# Motor-Board-Rev1.net
KiCad netlist of a schematic drawn in EAGLE
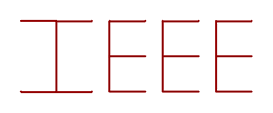
[diagram p0: schematic, sheet 1]
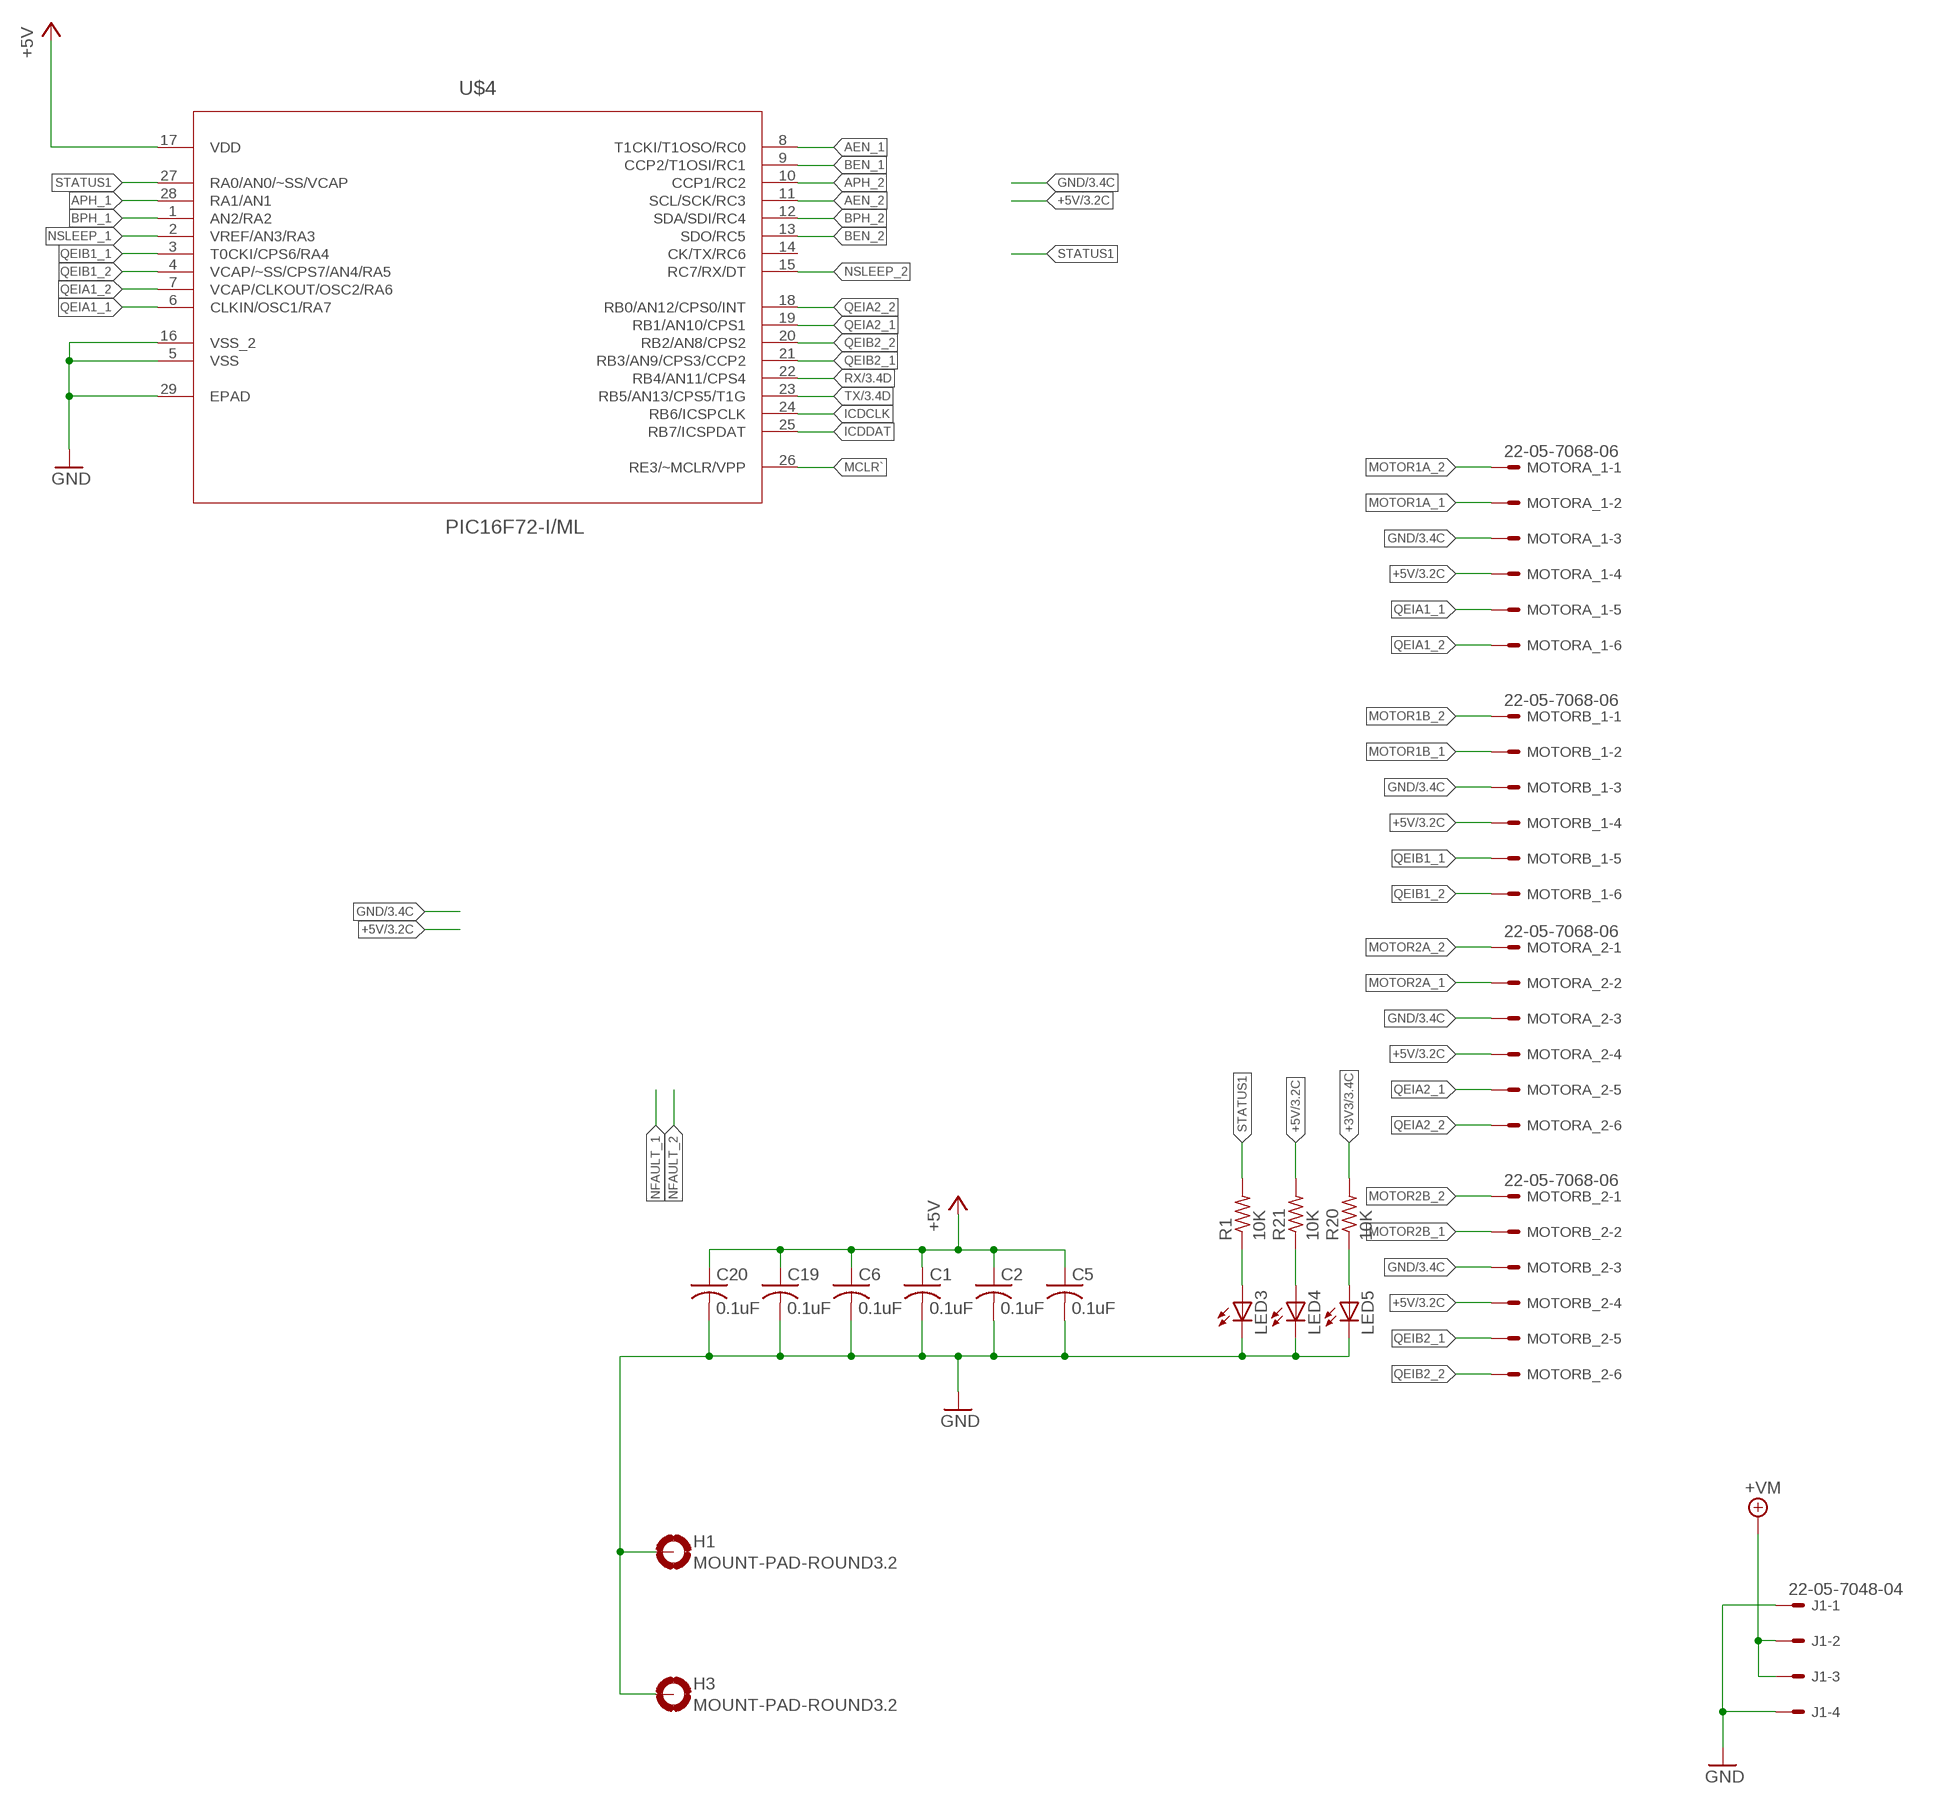
[diagram p1: schematic, sheet 2, part 1 of 2]
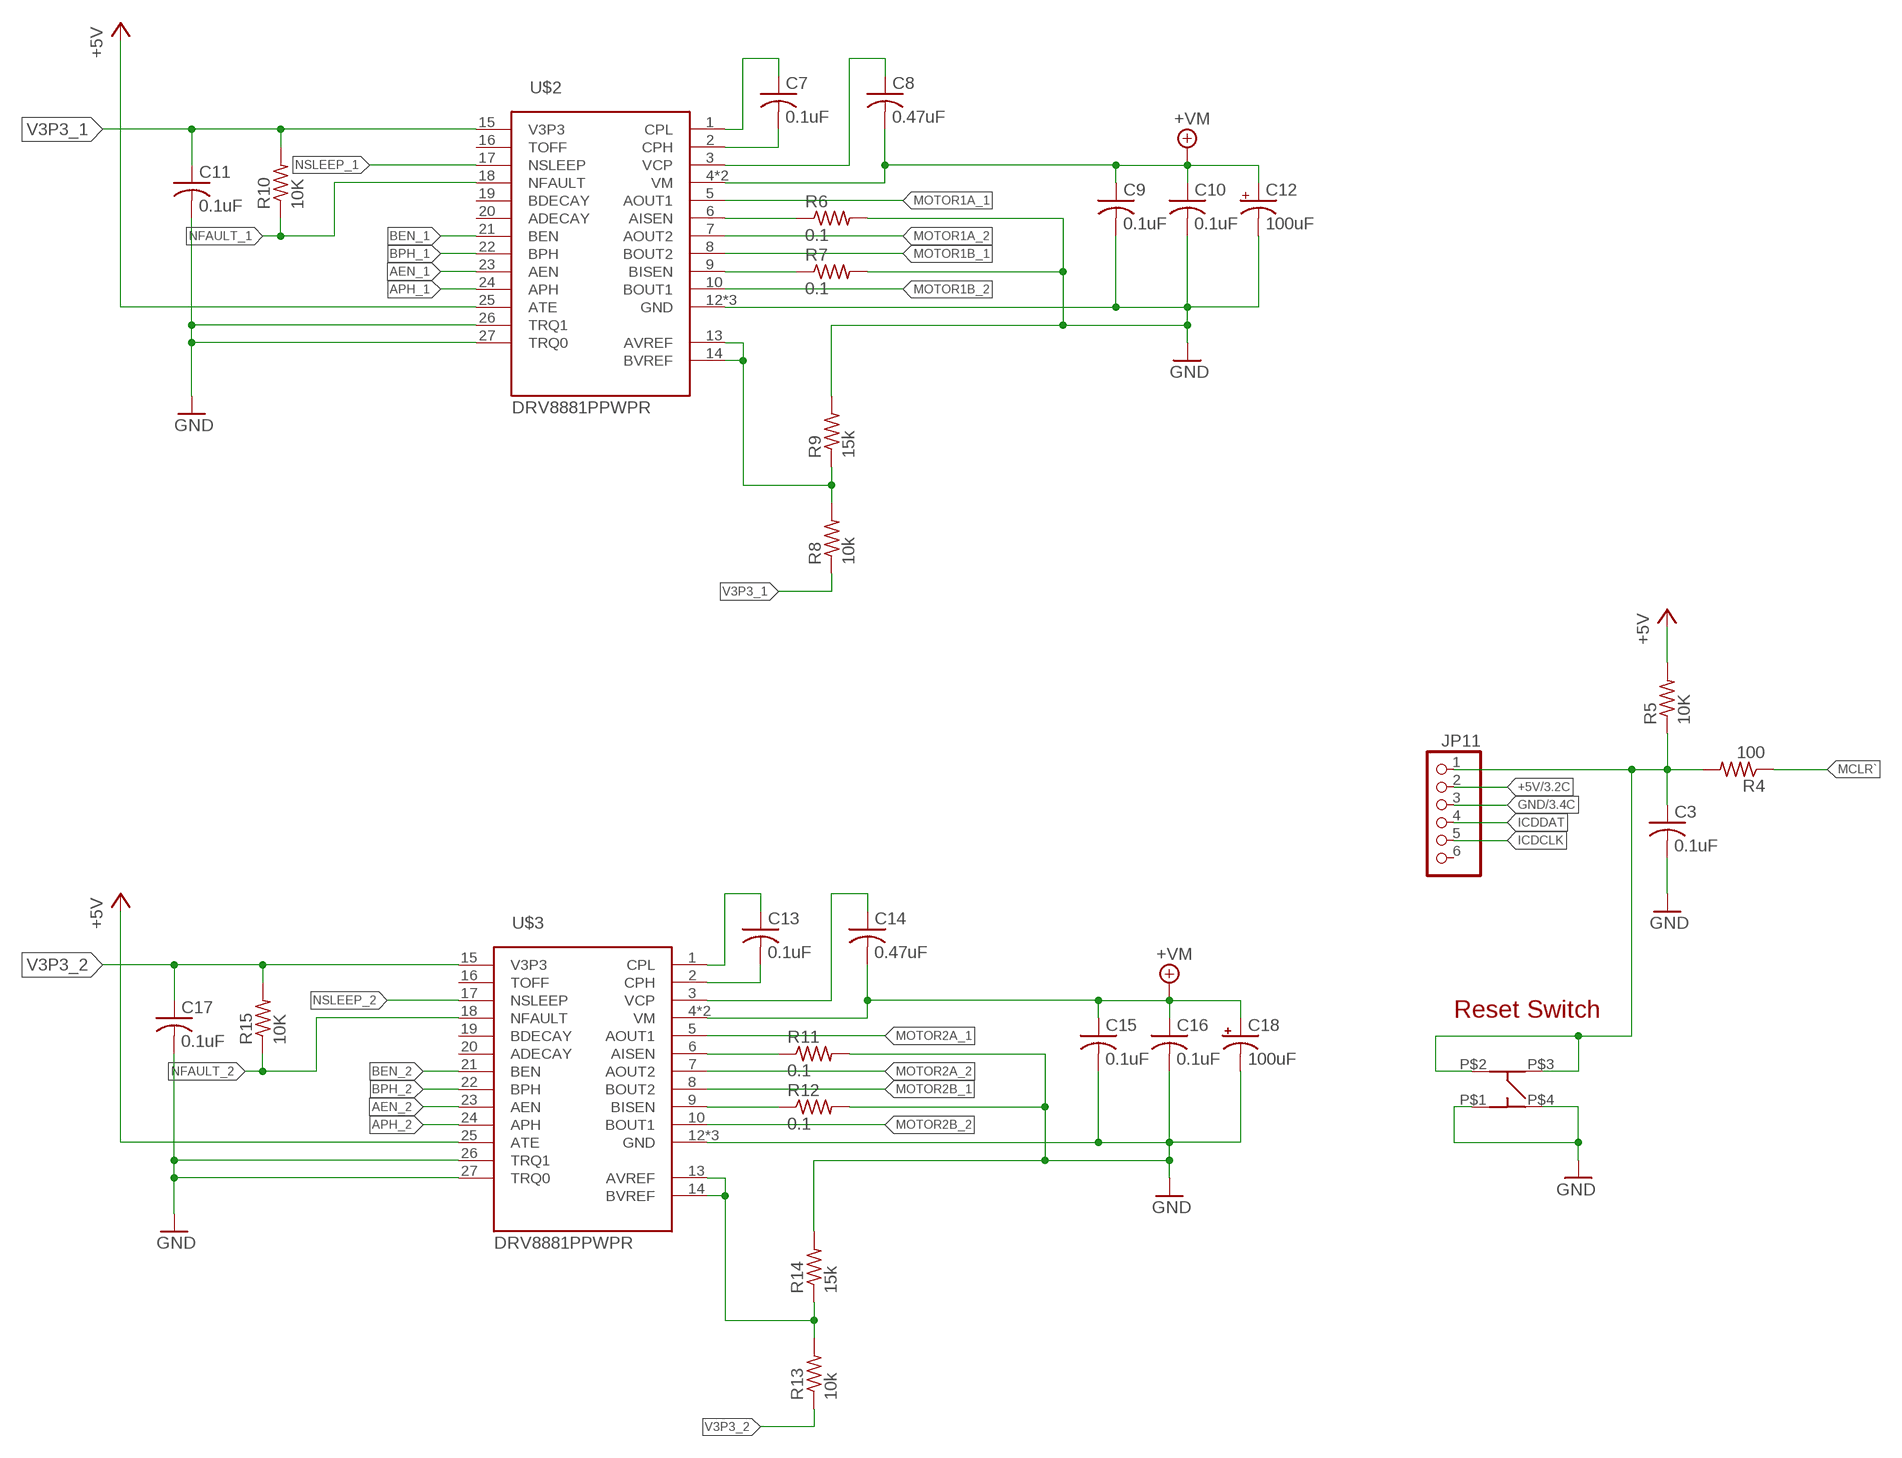
[diagram p2: schematic, sheet 2, part 2 of 2]
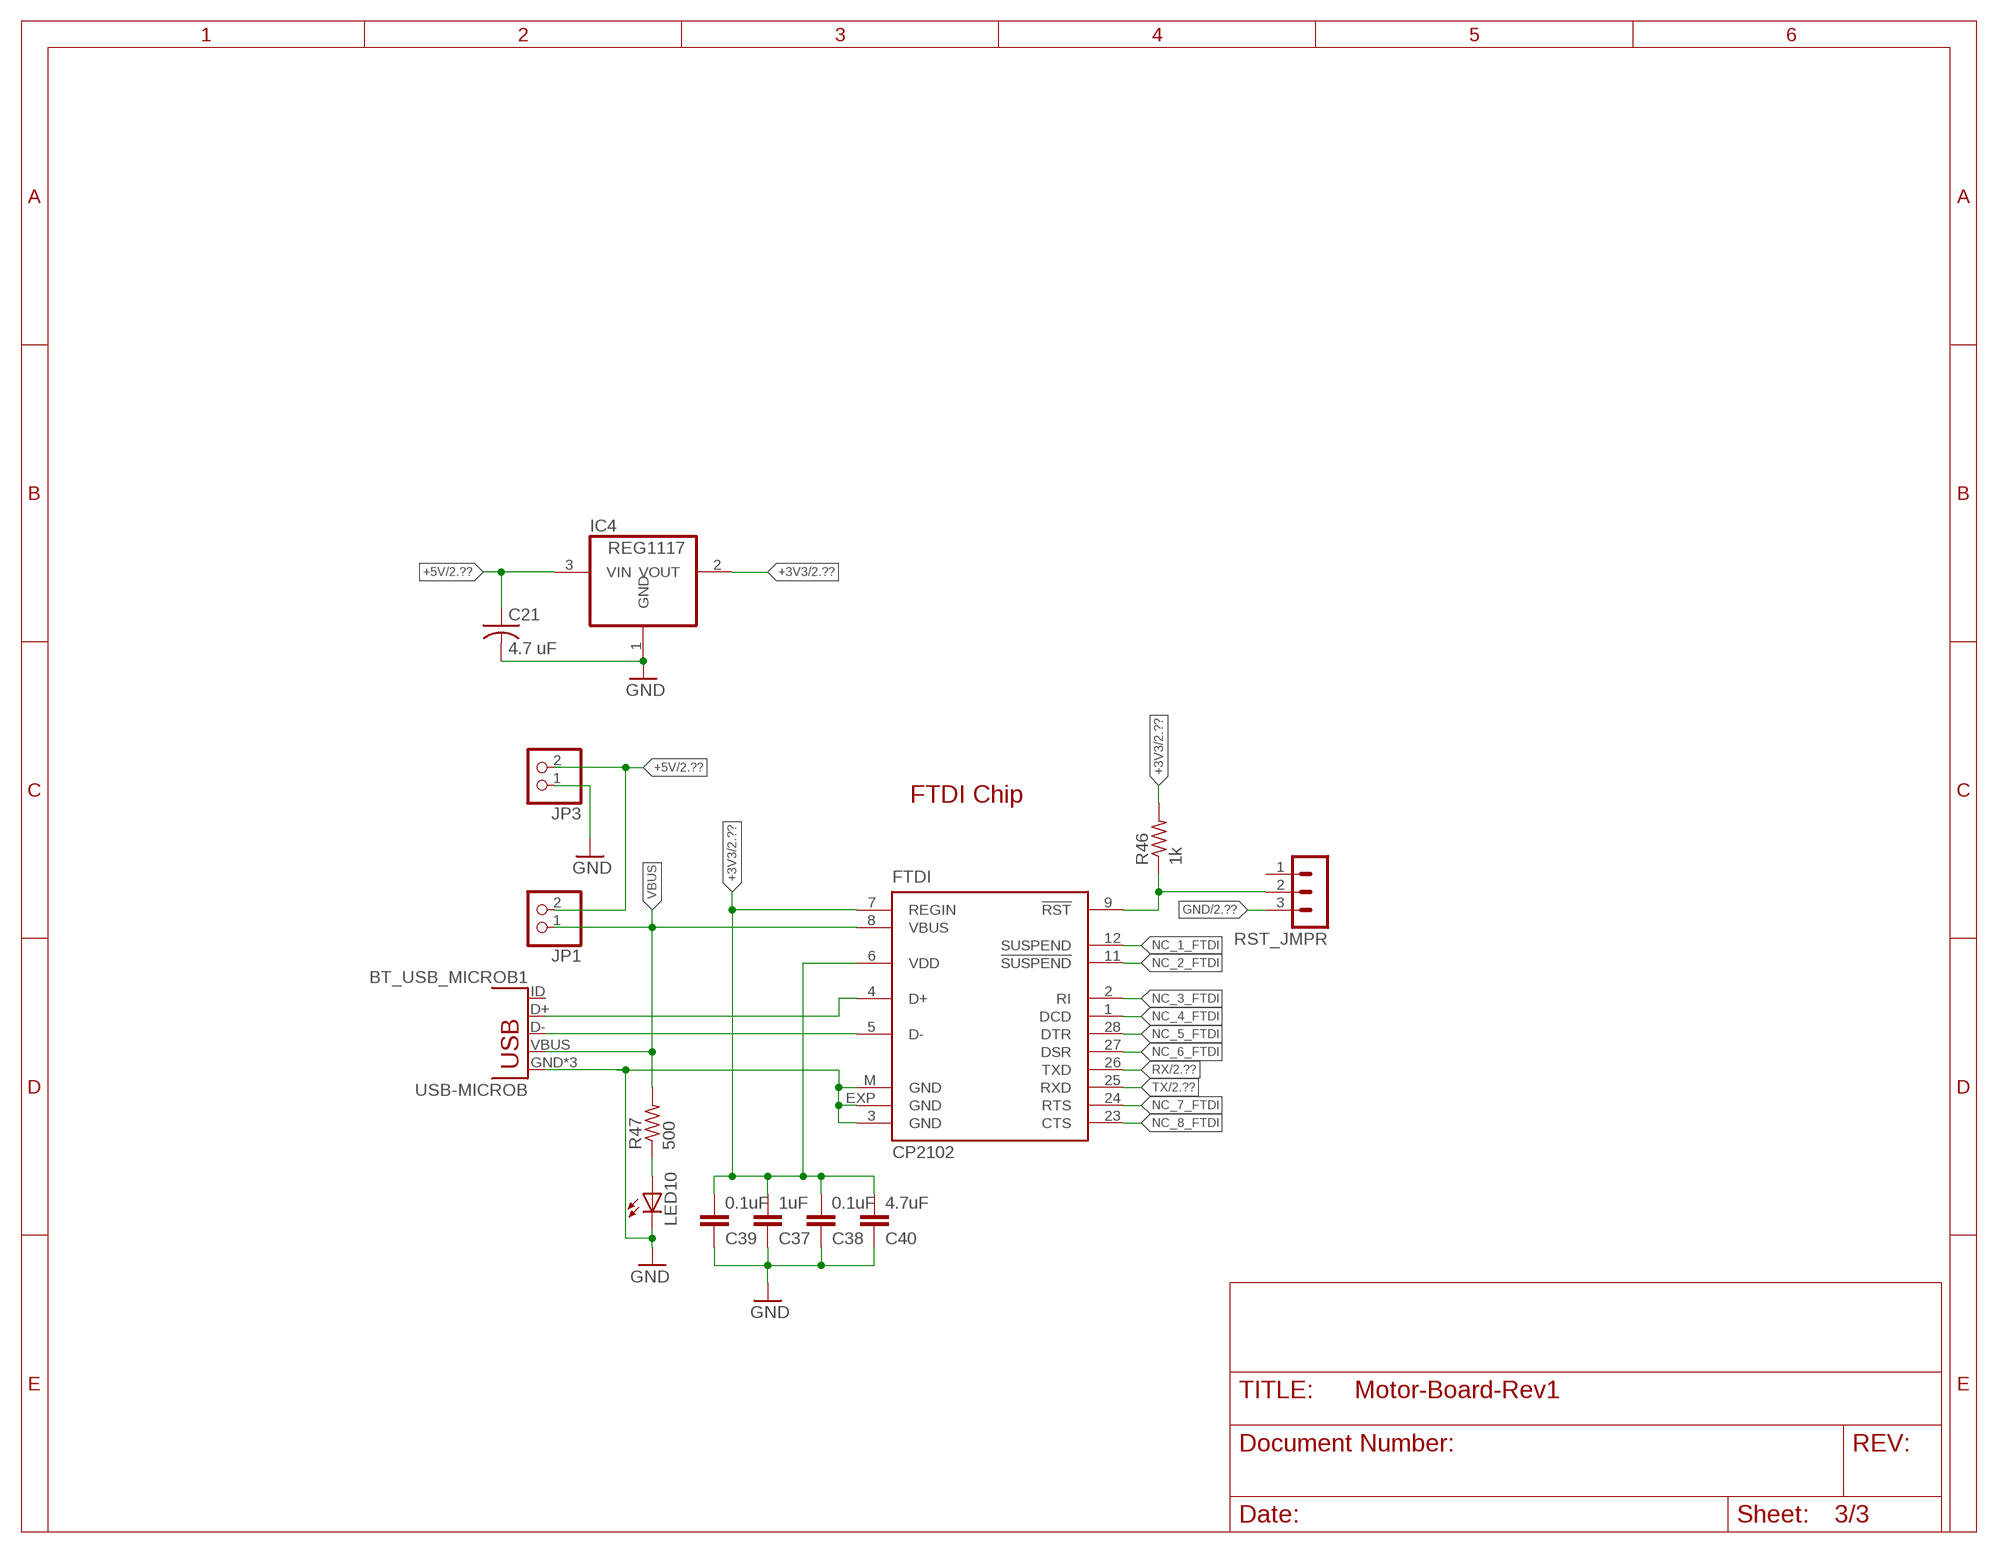
[diagram p3: schematic, sheet 3]

(export (version "E")
  (design (tool "Eeschema 10.0.6"))
  (components
    (comp (ref "U$1")
      (value "LOGO")
      (footprint "eagle-import:IEEE-LOGO")
      (libsource (lib "eagle-import") (part "LOGO"))
    )
    (comp (ref "C1")
      (value "0.1uF")
      (footprint "eagle-import:C0805")
      (libsource (lib "eagle-import") (part "C-USC0805"))
    )
    (comp (ref "C2")
      (value "0.1uF")
      (footprint "eagle-import:C0805")
      (libsource (lib "eagle-import") (part "C-USC0805"))
    )
    (comp (ref "C3")
      (value "0.1uF")
      (footprint "eagle-import:C0805")
      (libsource (lib "eagle-import") (part "C-USC0805"))
    )
    (comp (ref "C5")
      (value "0.1uF")
      (footprint "eagle-import:C0805")
      (libsource (lib "eagle-import") (part "C-USC0805"))
    )
    (comp (ref "C6")
      (value "0.1uF")
      (footprint "eagle-import:C0805")
      (libsource (lib "eagle-import") (part "C-USC0805"))
    )
    (comp (ref "C7")
      (value "0.1uF")
      (footprint "eagle-import:C0402")
      (libsource (lib "eagle-import") (part "C-USC0402"))
    )
    (comp (ref "C8")
      (value "0.47uF")
      (footprint "eagle-import:C0402")
      (libsource (lib "eagle-import") (part "C-USC0402"))
    )
    (comp (ref "C9")
      (value "0.1uF")
      (footprint "eagle-import:C0402")
      (libsource (lib "eagle-import") (part "C-USC0402"))
    )
    (comp (ref "C10")
      (value "0.1uF")
      (footprint "eagle-import:C0402")
      (libsource (lib "eagle-import") (part "C-USC0402"))
    )
    (comp (ref "C11")
      (value "0.1uF")
      (footprint "eagle-import:C0402")
      (libsource (lib "eagle-import") (part "C-USC0402"))
    )
    (comp (ref "C12")
      (value "100uF")
      (footprint "eagle-import:EIA7343")
      (libsource (lib "eagle-import") (part "100UF-10V-10%(TANT)"))
    )
    (comp (ref "C13")
      (value "0.1uF")
      (footprint "eagle-import:C0402")
      (libsource (lib "eagle-import") (part "C-USC0402"))
    )
    (comp (ref "C14")
      (value "0.47uF")
      (footprint "eagle-import:C0402")
      (libsource (lib "eagle-import") (part "C-USC0402"))
    )
    (comp (ref "C15")
      (value "0.1uF")
      (footprint "eagle-import:C0402")
      (libsource (lib "eagle-import") (part "C-USC0402"))
    )
    (comp (ref "C16")
      (value "0.1uF")
      (footprint "eagle-import:C0402")
      (libsource (lib "eagle-import") (part "C-USC0402"))
    )
    (comp (ref "C17")
      (value "0.1uF")
      (footprint "eagle-import:C0402")
      (libsource (lib "eagle-import") (part "C-USC0402"))
    )
    (comp (ref "C18")
      (value "100uF")
      (footprint "eagle-import:EIA7343")
      (libsource (lib "eagle-import") (part "100UF-10V-10%(TANT)"))
    )
    (comp (ref "C19")
      (value "0.1uF")
      (footprint "eagle-import:C0805")
      (libsource (lib "eagle-import") (part "C-USC0805"))
    )
    (comp (ref "C20")
      (value "0.1uF")
      (footprint "eagle-import:C0805")
      (libsource (lib "eagle-import") (part "C-USC0805"))
    )
    (comp (ref "H1")
      (value "MOUNT-PAD-ROUND3.2")
      (footprint "eagle-import:3,2-PAD")
      (libsource (lib "eagle-import") (part "MOUNT-PAD-ROUND3.2"))
    )
    (comp (ref "H3")
      (value "MOUNT-PAD-ROUND3.2")
      (footprint "eagle-import:3,2-PAD")
      (libsource (lib "eagle-import") (part "MOUNT-PAD-ROUND3.2"))
    )
    (comp (ref "J1")
      (value "22-05-7048-04")
      (footprint "eagle-import:7395-04")
      (libsource (lib "eagle-import") (part "22-?-0405-7048"))
    )
    (comp (ref "JP11")
      (value "PINHD-1X6/90")
      (footprint "eagle-import:1X06_90")
      (libsource (lib "eagle-import") (part "PINHD-1X6/90"))
    )
    (comp (ref "LED3")
      (value "LEDSML0603")
      (footprint "eagle-import:SML0603")
      (libsource (lib "eagle-import") (part "LEDSML0603"))
    )
    (comp (ref "LED4")
      (value "LEDSML0603")
      (footprint "eagle-import:SML0603")
      (libsource (lib "eagle-import") (part "LEDSML0603"))
    )
    (comp (ref "LED5")
      (value "LEDSML0603")
      (footprint "eagle-import:SML0603")
      (libsource (lib "eagle-import") (part "LEDSML0603"))
    )
    (comp (ref "MOTORA_1")
      (value "22-05-7068-06")
      (footprint "eagle-import:7395-06")
      (libsource (lib "eagle-import") (part "22-?-0605-7068"))
    )
    (comp (ref "MOTORA_2")
      (value "22-05-7068-06")
      (footprint "eagle-import:7395-06")
      (libsource (lib "eagle-import") (part "22-?-0605-7068"))
    )
    (comp (ref "MOTORB_1")
      (value "22-05-7068-06")
      (footprint "eagle-import:7395-06")
      (libsource (lib "eagle-import") (part "22-?-0605-7068"))
    )
    (comp (ref "MOTORB_2")
      (value "22-05-7068-06")
      (footprint "eagle-import:7395-06")
      (libsource (lib "eagle-import") (part "22-?-0605-7068"))
    )
    (comp (ref "R1")
      (value "10K")
      (footprint "eagle-import:R0805")
      (libsource (lib "eagle-import") (part "R-US_R0805"))
    )
    (comp (ref "R4")
      (value "100")
      (footprint "eagle-import:R0805")
      (libsource (lib "eagle-import") (part "R-US_R0805"))
    )
    (comp (ref "R5")
      (value "10K")
      (footprint "eagle-import:R0805")
      (libsource (lib "eagle-import") (part "R-US_R0805"))
    )
    (comp (ref "R6")
      (value "0.1")
      (footprint "eagle-import:R1206")
      (libsource (lib "eagle-import") (part "R-US_R1206"))
    )
    (comp (ref "R7")
      (value "0.1")
      (footprint "eagle-import:R1206")
      (libsource (lib "eagle-import") (part "R-US_R1206"))
    )
    (comp (ref "R8")
      (value "10k")
      (footprint "eagle-import:R0402")
      (libsource (lib "eagle-import") (part "R-US_R0402"))
    )
    (comp (ref "R9")
      (value "15k")
      (footprint "eagle-import:R0402")
      (libsource (lib "eagle-import") (part "R-US_R0402"))
    )
    (comp (ref "R10")
      (value "10K")
      (footprint "eagle-import:R1206")
      (libsource (lib "eagle-import") (part "R-US_R1206"))
    )
    (comp (ref "R11")
      (value "0.1")
      (footprint "eagle-import:R1206")
      (libsource (lib "eagle-import") (part "R-US_R1206"))
    )
    (comp (ref "R12")
      (value "0.1")
      (footprint "eagle-import:R1206")
      (libsource (lib "eagle-import") (part "R-US_R1206"))
    )
    (comp (ref "R13")
      (value "10k")
      (footprint "eagle-import:R0402")
      (libsource (lib "eagle-import") (part "R-US_R0402"))
    )
    (comp (ref "R14")
      (value "15k")
      (footprint "eagle-import:R0402")
      (libsource (lib "eagle-import") (part "R-US_R0402"))
    )
    (comp (ref "R15")
      (value "10K")
      (footprint "eagle-import:R1206")
      (libsource (lib "eagle-import") (part "R-US_R1206"))
    )
    (comp (ref "R20")
      (value "10K")
      (footprint "eagle-import:R0805")
      (libsource (lib "eagle-import") (part "R-US_R0805"))
    )
    (comp (ref "R21")
      (value "10K")
      (footprint "eagle-import:R0805")
      (libsource (lib "eagle-import") (part "R-US_R0805"))
    )
    (comp (ref "TOUCH_RESET")
      (value "RESET")
      (footprint "eagle-import:MC32882_FINAL")
      (libsource (lib "eagle-import") (part "MC32882_SW"))
    )
    (comp (ref "U$2")
      (value "DRV8881PPWPR")
      (footprint "eagle-import:TSSOP-28")
      (libsource (lib "eagle-import") (part "DRV8881PPWPR"))
    )
    (comp (ref "U$3")
      (value "DRV8881PPWPR")
      (footprint "eagle-import:TSSOP-28")
      (libsource (lib "eagle-import") (part "DRV8881PPWPR"))
    )
    (comp (ref "U$4")
      (value "PIC16F72-I/ML")
      (footprint "eagle-import:QFN65P600X600X100-28N")
      (libsource (lib "eagle-import") (part "PIC16F72-I/ML"))
    )
    (comp (ref "BT_USB_MICROB1")
      (value "USB-MICROB")
      (footprint "eagle-import:USB-MICROB")
      (libsource (lib "eagle-import") (part "USB-MICROB"))
    )
    (comp (ref "C21")
      (value "4.7 uF")
      (footprint "eagle-import:C0805")
      (libsource (lib "eagle-import") (part "C-USC0805"))
    )
    (comp (ref "C37")
      (value "1uF")
      (footprint "eagle-import:C0805")
      (libsource (lib "eagle-import") (part "C-EUC0805"))
    )
    (comp (ref "C38")
      (value "0.1uF")
      (footprint "eagle-import:C0805")
      (libsource (lib "eagle-import") (part "C-EUC0805"))
    )
    (comp (ref "C39")
      (value "0.1uF")
      (footprint "eagle-import:C0805")
      (libsource (lib "eagle-import") (part "C-EUC0805"))
    )
    (comp (ref "C40")
      (value "4.7uF")
      (footprint "eagle-import:C0805")
      (libsource (lib "eagle-import") (part "C-EUC0805"))
    )
    (comp (ref "FTDI")
      (value "CP2102")
      (footprint "eagle-import:MLP28")
      (fields (field (name "MF") "FARNELL") (field (name "MPN") "CP2102-GM"))
      (libsource (lib "eagle-import") (part "CP2102"))
    )
    (comp (ref "IC4")
      (value "REG1117")
      (footprint "eagle-import:SOT223")
      (libsource (lib "eagle-import") (part "REG1117"))
    )
    (comp (ref "JP1")
      (value "PINHD-1X2")
      (footprint "eagle-import:1X02")
      (libsource (lib "eagle-import") (part "PINHD-1X2"))
    )
    (comp (ref "JP3")
      (value "PINHD-1X2")
      (footprint "eagle-import:1X02")
      (libsource (lib "eagle-import") (part "PINHD-1X2"))
    )
    (comp (ref "LED10")
      (value "LEDSML0603")
      (footprint "eagle-import:SML0603")
      (libsource (lib "eagle-import") (part "LEDSML0603"))
    )
    (comp (ref "R46")
      (value "1k")
      (footprint "eagle-import:R0805")
      (libsource (lib "eagle-import") (part "resistor_R-US_R0805"))
    )
    (comp (ref "R47")
      (value "500")
      (footprint "eagle-import:R0805")
      (libsource (lib "eagle-import") (part "resistor_R-US_R0805"))
    )
    (comp (ref "RST_JMPR")
      (value "MA03-1")
      (footprint "eagle-import:MA03-1")
      (libsource (lib "eagle-import") (part "MA03-1"))
    )
  )
  (nets
    (net (code "1") (name "+3V3") (class "Default")
      (node (ref "C37") (pin "2") (pinfunction "2_2") (pintype "passive"))
      (node (ref "C38") (pin "2") (pinfunction "2_2") (pintype "passive"))
      (node (ref "C39") (pin "2") (pinfunction "2_2") (pintype "passive"))
      (node (ref "C40") (pin "2") (pinfunction "2_2") (pintype "passive"))
      (node (ref "FTDI") (pin "6") (pinfunction "VDD_6") (pintype "power_in"))
      (node (ref "FTDI") (pin "7") (pinfunction "REGIN_7") (pintype "passive"))
      (node (ref "IC4") (pin "2") (pinfunction "VOUT_2") (pintype "output"))
      (node (ref "R20") (pin "2") (pinfunction "2_2") (pintype "passive"))
      (node (ref "R46") (pin "2") (pinfunction "2_2") (pintype "passive"))
    )
    (net (code "2") (name "+5V") (class "Default")
      (node (ref "C1") (pin "1") (pinfunction "1_1") (pintype "passive"))
      (node (ref "C19") (pin "1") (pinfunction "1_1") (pintype "passive"))
      (node (ref "C2") (pin "1") (pinfunction "1_1") (pintype "passive"))
      (node (ref "C20") (pin "1") (pinfunction "1_1") (pintype "passive"))
      (node (ref "C21") (pin "1") (pinfunction "1_1") (pintype "passive"))
      (node (ref "C5") (pin "1") (pinfunction "1_1") (pintype "passive"))
      (node (ref "C6") (pin "1") (pinfunction "1_1") (pintype "passive"))
      (node (ref "IC4") (pin "3") (pinfunction "VIN_3") (pintype "input"))
      (node (ref "JP1") (pin "2") (pinfunction "2_2") (pintype "passive"))
      (node (ref "JP11") (pin "2") (pinfunction "2_2") (pintype "passive"))
      (node (ref "JP3") (pin "2") (pinfunction "2_2") (pintype "passive"))
      (node (ref "MOTORA_1") (pin "4") (pinfunction "S_4") (pintype "passive"))
      (node (ref "MOTORA_2") (pin "4") (pinfunction "S_4") (pintype "passive"))
      (node (ref "MOTORB_1") (pin "4") (pinfunction "S_4") (pintype "passive"))
      (node (ref "MOTORB_2") (pin "4") (pinfunction "S_4") (pintype "passive"))
      (node (ref "R21") (pin "2") (pinfunction "2_2") (pintype "passive"))
      (node (ref "R5") (pin "2") (pinfunction "2_2") (pintype "passive"))
      (node (ref "U$2") (pin "25") (pinfunction "ATE_25") (pintype "bidirectional"))
      (node (ref "U$3") (pin "25") (pinfunction "ATE_25") (pintype "bidirectional"))
      (node (ref "U$4") (pin "17") (pinfunction "VDD_17") (pintype "power_in"))
    )
    (net (code "3") (name "+7V") (class "Default")
      (node (ref "C10") (pin "1") (pinfunction "1_1") (pintype "passive"))
      (node (ref "C12") (pin "A") (pinfunction "+_A") (pintype "passive"))
      (node (ref "C14") (pin "2") (pinfunction "2_2") (pintype "passive"))
      (node (ref "C15") (pin "1") (pinfunction "1_1") (pintype "passive"))
      (node (ref "C16") (pin "1") (pinfunction "1_1") (pintype "passive"))
      (node (ref "C18") (pin "A") (pinfunction "+_A") (pintype "passive"))
      (node (ref "C8") (pin "2") (pinfunction "2_2") (pintype "passive"))
      (node (ref "C9") (pin "1") (pinfunction "1_1") (pintype "passive"))
      (node (ref "J1") (pin "2") (pinfunction "S_2") (pintype "passive"))
      (node (ref "J1") (pin "3") (pinfunction "S_3") (pintype "passive"))
      (node (ref "U$2") (pin "11") (pinfunction "VM_11") (pintype "bidirectional"))
      (node (ref "U$2") (pin "4") (pinfunction "VM_4") (pintype "bidirectional"))
      (node (ref "U$3") (pin "11") (pinfunction "VM_11") (pintype "bidirectional"))
      (node (ref "U$3") (pin "4") (pinfunction "VM_4") (pintype "bidirectional"))
    )
    (net (code "4") (name "AEN_1") (class "Default")
      (node (ref "U$2") (pin "23") (pinfunction "AEN_23") (pintype "bidirectional"))
      (node (ref "U$4") (pin "8") (pinfunction "T1CKI/T1OSO/RC0_8") (pintype "bidirectional"))
    )
    (net (code "5") (name "AEN_2") (class "Default")
      (node (ref "U$3") (pin "23") (pinfunction "AEN_23") (pintype "bidirectional"))
      (node (ref "U$4") (pin "11") (pinfunction "SCL/SCK/RC3_11") (pintype "bidirectional"))
    )
    (net (code "6") (name "APH_1") (class "Default")
      (node (ref "U$2") (pin "24") (pinfunction "APH_24") (pintype "bidirectional"))
      (node (ref "U$4") (pin "28") (pinfunction "RA1/AN1_28") (pintype "bidirectional"))
    )
    (net (code "7") (name "APH_2") (class "Default")
      (node (ref "U$3") (pin "24") (pinfunction "APH_24") (pintype "bidirectional"))
      (node (ref "U$4") (pin "10") (pinfunction "CCP1/RC2_10") (pintype "bidirectional"))
    )
    (net (code "8") (name "BEN_1") (class "Default")
      (node (ref "U$2") (pin "21") (pinfunction "BEN_21") (pintype "bidirectional"))
      (node (ref "U$4") (pin "9") (pinfunction "CCP2/T1OSI/RC1_9") (pintype "bidirectional"))
    )
    (net (code "9") (name "BEN_2") (class "Default")
      (node (ref "U$3") (pin "21") (pinfunction "BEN_21") (pintype "bidirectional"))
      (node (ref "U$4") (pin "13") (pinfunction "SDO/RC5_13") (pintype "bidirectional"))
    )
    (net (code "10") (name "BPH_1") (class "Default")
      (node (ref "U$2") (pin "22") (pinfunction "BPH_22") (pintype "bidirectional"))
      (node (ref "U$4") (pin "1") (pinfunction "AN2/RA2_1") (pintype "bidirectional"))
    )
    (net (code "11") (name "BPH_2") (class "Default")
      (node (ref "U$3") (pin "22") (pinfunction "BPH_22") (pintype "bidirectional"))
      (node (ref "U$4") (pin "12") (pinfunction "SDA/SDI/RC4_12") (pintype "bidirectional"))
    )
    (net (code "12") (name "GND") (class "Default")
      (node (ref "BT_USB_MICROB1") (pin "GND") (pinfunction "GND_GND") (pintype "bidirectional"))
      (node (ref "BT_USB_MICROB1") (pin "MT1") (pinfunction "GND_MT1") (pintype "bidirectional"))
      (node (ref "BT_USB_MICROB1") (pin "MT2") (pinfunction "GND_MT2") (pintype "bidirectional"))
      (node (ref "C1") (pin "2") (pinfunction "2_2") (pintype "passive"))
      (node (ref "C10") (pin "2") (pinfunction "2_2") (pintype "passive"))
      (node (ref "C11") (pin "2") (pinfunction "2_2") (pintype "passive"))
      (node (ref "C12") (pin "C") (pinfunction "-_C") (pintype "passive"))
      (node (ref "C15") (pin "2") (pinfunction "2_2") (pintype "passive"))
      (node (ref "C16") (pin "2") (pinfunction "2_2") (pintype "passive"))
      (node (ref "C17") (pin "2") (pinfunction "2_2") (pintype "passive"))
      (node (ref "C18") (pin "C") (pinfunction "-_C") (pintype "passive"))
      (node (ref "C19") (pin "2") (pinfunction "2_2") (pintype "passive"))
      (node (ref "C2") (pin "2") (pinfunction "2_2") (pintype "passive"))
      (node (ref "C20") (pin "2") (pinfunction "2_2") (pintype "passive"))
      (node (ref "C21") (pin "2") (pinfunction "2_2") (pintype "passive"))
      (node (ref "C3") (pin "2") (pinfunction "2_2") (pintype "passive"))
      (node (ref "C37") (pin "1") (pinfunction "1_1") (pintype "passive"))
      (node (ref "C38") (pin "1") (pinfunction "1_1") (pintype "passive"))
      (node (ref "C39") (pin "1") (pinfunction "1_1") (pintype "passive"))
      (node (ref "C40") (pin "1") (pinfunction "1_1") (pintype "passive"))
      (node (ref "C5") (pin "2") (pinfunction "2_2") (pintype "passive"))
      (node (ref "C6") (pin "2") (pinfunction "2_2") (pintype "passive"))
      (node (ref "C9") (pin "2") (pinfunction "2_2") (pintype "passive"))
      (node (ref "FTDI") (pin "3") (pinfunction "GND_3") (pintype "power_in"))
      (node (ref "FTDI") (pin "EXP") (pinfunction "GND_EXP") (pintype "power_in"))
      (node (ref "FTDI") (pin "M") (pinfunction "GND_M") (pintype "power_in"))
      (node (ref "H1") (pin "B3,2") (pinfunction "MOUNT_B3,2") (pintype "passive"))
      (node (ref "H3") (pin "B3,2") (pinfunction "MOUNT_B3,2") (pintype "passive"))
      (node (ref "IC4") (pin "1") (pinfunction "GND_1") (pintype "power_in"))
      (node (ref "J1") (pin "1") (pinfunction "S_1") (pintype "passive"))
      (node (ref "J1") (pin "4") (pinfunction "S_4") (pintype "passive"))
      (node (ref "JP11") (pin "3") (pinfunction "3_3") (pintype "passive"))
      (node (ref "JP3") (pin "1") (pinfunction "1_1") (pintype "passive"))
      (node (ref "LED10") (pin "C") (pinfunction "C_C") (pintype "passive"))
      (node (ref "LED3") (pin "C") (pinfunction "C_C") (pintype "passive"))
      (node (ref "LED4") (pin "C") (pinfunction "C_C") (pintype "passive"))
      (node (ref "LED5") (pin "C") (pinfunction "C_C") (pintype "passive"))
      (node (ref "MOTORA_1") (pin "3") (pinfunction "S_3") (pintype "passive"))
      (node (ref "MOTORA_2") (pin "3") (pinfunction "S_3") (pintype "passive"))
      (node (ref "MOTORB_1") (pin "3") (pinfunction "S_3") (pintype "passive"))
      (node (ref "MOTORB_2") (pin "3") (pinfunction "S_3") (pintype "passive"))
      (node (ref "R11") (pin "2") (pinfunction "2_2") (pintype "passive"))
      (node (ref "R12") (pin "2") (pinfunction "2_2") (pintype "passive"))
      (node (ref "R14") (pin "2") (pinfunction "2_2") (pintype "passive"))
      (node (ref "R6") (pin "2") (pinfunction "2_2") (pintype "passive"))
      (node (ref "R7") (pin "2") (pinfunction "2_2") (pintype "passive"))
      (node (ref "R9") (pin "2") (pinfunction "2_2") (pintype "passive"))
      (node (ref "RST_JMPR") (pin "3") (pinfunction "3_3") (pintype "passive"))
      (node (ref "TOUCH_RESET") (pin "P$1") (pinfunction "P1_P$1") (pintype "bidirectional"))
      (node (ref "TOUCH_RESET") (pin "P$4") (pinfunction "P4_P$4") (pintype "bidirectional"))
      (node (ref "U$2") (pin "12") (pinfunction "GND_12") (pintype "bidirectional"))
      (node (ref "U$2") (pin "26") (pinfunction "TRQ1_26") (pintype "bidirectional"))
      (node (ref "U$2") (pin "27") (pinfunction "TRQ0_27") (pintype "bidirectional"))
      (node (ref "U$2") (pin "28") (pinfunction "GND_28") (pintype "bidirectional"))
      (node (ref "U$2") (pin "EXP") (pinfunction "GND_EXP") (pintype "bidirectional"))
      (node (ref "U$3") (pin "12") (pinfunction "GND_12") (pintype "bidirectional"))
      (node (ref "U$3") (pin "26") (pinfunction "TRQ1_26") (pintype "bidirectional"))
      (node (ref "U$3") (pin "27") (pinfunction "TRQ0_27") (pintype "bidirectional"))
      (node (ref "U$3") (pin "28") (pinfunction "GND_28") (pintype "bidirectional"))
      (node (ref "U$3") (pin "EXP") (pinfunction "GND_EXP") (pintype "bidirectional"))
      (node (ref "U$4") (pin "16") (pinfunction "VSS_2_16") (pintype "power_in"))
      (node (ref "U$4") (pin "29") (pinfunction "EPAD_29") (pintype "passive"))
      (node (ref "U$4") (pin "5") (pinfunction "VSS_5") (pintype "power_in"))
    )
    (net (code "13") (name "ICDCLK") (class "Default")
      (node (ref "JP11") (pin "5") (pinfunction "5_5") (pintype "passive"))
      (node (ref "U$4") (pin "24") (pinfunction "RB6/ICSPCLK_24") (pintype "bidirectional"))
    )
    (net (code "14") (name "ICDDAT") (class "Default")
      (node (ref "JP11") (pin "4") (pinfunction "4_4") (pintype "passive"))
      (node (ref "U$4") (pin "25") (pinfunction "RB7/ICSPDAT_25") (pintype "bidirectional"))
    )
    (net (code "15") (name "MCLR`") (class "Default")
      (node (ref "R4") (pin "1") (pinfunction "1_1") (pintype "passive"))
      (node (ref "U$4") (pin "26") (pinfunction "RE3/~{MCLR/VPP}_26") (pintype "bidirectional"))
    )
    (net (code "16") (name "MOTOR1A_1") (class "Default")
      (node (ref "MOTORA_1") (pin "2") (pinfunction "S_2") (pintype "passive"))
      (node (ref "U$2") (pin "5") (pinfunction "AOUT1_5") (pintype "bidirectional"))
    )
    (net (code "17") (name "MOTOR1A_2") (class "Default")
      (node (ref "MOTORA_1") (pin "1") (pinfunction "S_1") (pintype "passive"))
      (node (ref "U$2") (pin "7") (pinfunction "AOUT2_7") (pintype "bidirectional"))
    )
    (net (code "18") (name "MOTOR1B_1") (class "Default")
      (node (ref "MOTORB_1") (pin "2") (pinfunction "S_2") (pintype "passive"))
      (node (ref "U$2") (pin "8") (pinfunction "BOUT2_8") (pintype "bidirectional"))
    )
    (net (code "19") (name "MOTOR1B_2") (class "Default")
      (node (ref "MOTORB_1") (pin "1") (pinfunction "S_1") (pintype "passive"))
      (node (ref "U$2") (pin "10") (pinfunction "BOUT1_10") (pintype "bidirectional"))
    )
    (net (code "20") (name "MOTOR2A_1") (class "Default")
      (node (ref "MOTORA_2") (pin "2") (pinfunction "S_2") (pintype "passive"))
      (node (ref "U$3") (pin "5") (pinfunction "AOUT1_5") (pintype "bidirectional"))
    )
    (net (code "21") (name "MOTOR2A_2") (class "Default")
      (node (ref "MOTORA_2") (pin "1") (pinfunction "S_1") (pintype "passive"))
      (node (ref "U$3") (pin "7") (pinfunction "AOUT2_7") (pintype "bidirectional"))
    )
    (net (code "22") (name "MOTOR2B_1") (class "Default")
      (node (ref "MOTORB_2") (pin "2") (pinfunction "S_2") (pintype "passive"))
      (node (ref "U$3") (pin "8") (pinfunction "BOUT2_8") (pintype "bidirectional"))
    )
    (net (code "23") (name "MOTOR2B_2") (class "Default")
      (node (ref "MOTORB_2") (pin "1") (pinfunction "S_1") (pintype "passive"))
      (node (ref "U$3") (pin "10") (pinfunction "BOUT1_10") (pintype "bidirectional"))
    )
    (net (code "24") (name "NC_1_FTDI") (class "Default")
      (node (ref "FTDI") (pin "12") (pinfunction "SUSPEND_12") (pintype "output"))
    )
    (net (code "25") (name "NC_2_FTDI") (class "Default")
      (node (ref "FTDI") (pin "11") (pinfunction "~{SUSPEND}_11") (pintype "output"))
    )
    (net (code "26") (name "NC_3_FTDI") (class "Default")
      (node (ref "FTDI") (pin "2") (pinfunction "RI_2") (pintype "input"))
    )
    (net (code "27") (name "NC_4_FTDI") (class "Default")
      (node (ref "FTDI") (pin "1") (pinfunction "DCD_1") (pintype "input"))
    )
    (net (code "28") (name "NC_5_FTDI") (class "Default")
      (node (ref "FTDI") (pin "28") (pinfunction "DTR_28") (pintype "output"))
    )
    (net (code "29") (name "NC_6_FTDI") (class "Default")
      (node (ref "FTDI") (pin "27") (pinfunction "DSR_27") (pintype "input"))
    )
    (net (code "30") (name "NC_7_FTDI") (class "Default")
      (node (ref "FTDI") (pin "24") (pinfunction "RTS_24") (pintype "output"))
    )
    (net (code "31") (name "NC_8_FTDI") (class "Default")
      (node (ref "FTDI") (pin "23") (pinfunction "CTS_23") (pintype "input"))
    )
    (net (code "32") (name "NFAULT_1") (class "Default")
      (node (ref "R10") (pin "1") (pinfunction "1_1") (pintype "passive"))
      (node (ref "U$2") (pin "18") (pinfunction "NFAULT_18") (pintype "bidirectional"))
    )
    (net (code "33") (name "NFAULT_2") (class "Default")
      (node (ref "R15") (pin "1") (pinfunction "1_1") (pintype "passive"))
      (node (ref "U$3") (pin "18") (pinfunction "NFAULT_18") (pintype "bidirectional"))
    )
    (net (code "34") (name "NSLEEP_1") (class "Default")
      (node (ref "U$2") (pin "17") (pinfunction "NSLEEP_17") (pintype "bidirectional"))
      (node (ref "U$4") (pin "2") (pinfunction "VREF/AN3/RA3_2") (pintype "bidirectional"))
    )
    (net (code "35") (name "NSLEEP_2") (class "Default")
      (node (ref "U$3") (pin "17") (pinfunction "NSLEEP_17") (pintype "bidirectional"))
      (node (ref "U$4") (pin "15") (pinfunction "RC7/RX/DT_15") (pintype "bidirectional"))
    )
    (net (code "36") (name "Net-(FTDI-D+)") (class "Default")
      (node (ref "BT_USB_MICROB1") (pin "D+") (pinfunction "D+_D+") (pintype "bidirectional"))
      (node (ref "FTDI") (pin "4") (pinfunction "D+_4") (pintype "bidirectional"))
    )
    (net (code "37") (name "Net-(FTDI-D-)") (class "Default")
      (node (ref "BT_USB_MICROB1") (pin "D-") (pinfunction "D-_D-") (pintype "bidirectional"))
      (node (ref "FTDI") (pin "5") (pinfunction "D-_5") (pintype "bidirectional"))
    )
    (net (code "38") (name "Net-(FTDI-~{RST})") (class "Default")
      (node (ref "FTDI") (pin "9") (pinfunction "~{RST}_9") (pintype "bidirectional"))
      (node (ref "R46") (pin "1") (pinfunction "1_1") (pintype "passive"))
      (node (ref "RST_JMPR") (pin "2") (pinfunction "2_2") (pintype "passive"))
    )
    (net (code "39") (name "Net-(LED3-PadA)") (class "Default")
      (node (ref "LED3") (pin "A") (pinfunction "A_A") (pintype "passive"))
      (node (ref "R1") (pin "1") (pinfunction "1_1") (pintype "passive"))
    )
    (net (code "40") (name "Net-(LED4-PadA)") (class "Default")
      (node (ref "LED4") (pin "A") (pinfunction "A_A") (pintype "passive"))
      (node (ref "R21") (pin "1") (pinfunction "1_1") (pintype "passive"))
    )
    (net (code "41") (name "Net-(LED5-PadA)") (class "Default")
      (node (ref "LED5") (pin "A") (pinfunction "A_A") (pintype "passive"))
      (node (ref "R20") (pin "1") (pinfunction "1_1") (pintype "passive"))
    )
    (net (code "42") (name "Net-(LED10-PadA)") (class "Default")
      (node (ref "LED10") (pin "A") (pinfunction "A_A") (pintype "passive"))
      (node (ref "R47") (pin "1") (pinfunction "1_1") (pintype "passive"))
    )
    (net (code "43") (name "Net-(TOUCH_RESET-P2)") (class "Default")
      (node (ref "C3") (pin "1") (pinfunction "1_1") (pintype "passive"))
      (node (ref "JP11") (pin "1") (pinfunction "1_1") (pintype "passive"))
      (node (ref "R4") (pin "2") (pinfunction "2_2") (pintype "passive"))
      (node (ref "R5") (pin "1") (pinfunction "1_1") (pintype "passive"))
      (node (ref "TOUCH_RESET") (pin "P$2") (pinfunction "P2_P$2") (pintype "bidirectional"))
      (node (ref "TOUCH_RESET") (pin "P$3") (pinfunction "P3_P$3") (pintype "bidirectional"))
    )
    (net (code "44") (name "Net-(U$2-AISEN)") (class "Default")
      (node (ref "R6") (pin "1") (pinfunction "1_1") (pintype "passive"))
      (node (ref "U$2") (pin "6") (pinfunction "AISEN_6") (pintype "bidirectional"))
    )
    (net (code "45") (name "Net-(U$2-AVREF)") (class "Default")
      (node (ref "R8") (pin "2") (pinfunction "2_2") (pintype "passive"))
      (node (ref "R9") (pin "1") (pinfunction "1_1") (pintype "passive"))
      (node (ref "U$2") (pin "13") (pinfunction "AVREF_13") (pintype "bidirectional"))
      (node (ref "U$2") (pin "14") (pinfunction "BVREF_14") (pintype "bidirectional"))
    )
    (net (code "46") (name "Net-(U$2-BISEN)") (class "Default")
      (node (ref "R7") (pin "1") (pinfunction "1_1") (pintype "passive"))
      (node (ref "U$2") (pin "9") (pinfunction "BISEN_9") (pintype "bidirectional"))
    )
    (net (code "47") (name "Net-(U$2-CPH)") (class "Default")
      (node (ref "C7") (pin "2") (pinfunction "2_2") (pintype "passive"))
      (node (ref "U$2") (pin "2") (pinfunction "CPH_2") (pintype "bidirectional"))
    )
    (net (code "48") (name "Net-(U$2-CPL)") (class "Default")
      (node (ref "C7") (pin "1") (pinfunction "1_1") (pintype "passive"))
      (node (ref "U$2") (pin "1") (pinfunction "CPL_1") (pintype "bidirectional"))
    )
    (net (code "49") (name "Net-(U$2-VCP)") (class "Default")
      (node (ref "C8") (pin "1") (pinfunction "1_1") (pintype "passive"))
      (node (ref "U$2") (pin "3") (pinfunction "VCP_3") (pintype "bidirectional"))
    )
    (net (code "50") (name "Net-(U$3-AISEN)") (class "Default")
      (node (ref "R11") (pin "1") (pinfunction "1_1") (pintype "passive"))
      (node (ref "U$3") (pin "6") (pinfunction "AISEN_6") (pintype "bidirectional"))
    )
    (net (code "51") (name "Net-(U$3-AVREF)") (class "Default")
      (node (ref "R13") (pin "2") (pinfunction "2_2") (pintype "passive"))
      (node (ref "R14") (pin "1") (pinfunction "1_1") (pintype "passive"))
      (node (ref "U$3") (pin "13") (pinfunction "AVREF_13") (pintype "bidirectional"))
      (node (ref "U$3") (pin "14") (pinfunction "BVREF_14") (pintype "bidirectional"))
    )
    (net (code "52") (name "Net-(U$3-BISEN)") (class "Default")
      (node (ref "R12") (pin "1") (pinfunction "1_1") (pintype "passive"))
      (node (ref "U$3") (pin "9") (pinfunction "BISEN_9") (pintype "bidirectional"))
    )
    (net (code "53") (name "Net-(U$3-CPH)") (class "Default")
      (node (ref "C13") (pin "2") (pinfunction "2_2") (pintype "passive"))
      (node (ref "U$3") (pin "2") (pinfunction "CPH_2") (pintype "bidirectional"))
    )
    (net (code "54") (name "Net-(U$3-CPL)") (class "Default")
      (node (ref "C13") (pin "1") (pinfunction "1_1") (pintype "passive"))
      (node (ref "U$3") (pin "1") (pinfunction "CPL_1") (pintype "bidirectional"))
    )
    (net (code "55") (name "Net-(U$3-VCP)") (class "Default")
      (node (ref "C14") (pin "1") (pinfunction "1_1") (pintype "passive"))
      (node (ref "U$3") (pin "3") (pinfunction "VCP_3") (pintype "bidirectional"))
    )
    (net (code "56") (name "QEIA1_1") (class "Default")
      (node (ref "MOTORA_1") (pin "5") (pinfunction "S_5") (pintype "passive"))
      (node (ref "U$4") (pin "6") (pinfunction "CLKIN/OSC1/RA7_6") (pintype "bidirectional"))
    )
    (net (code "57") (name "QEIA1_2") (class "Default")
      (node (ref "MOTORA_1") (pin "6") (pinfunction "S_6") (pintype "passive"))
      (node (ref "U$4") (pin "7") (pinfunction "VCAP/CLKOUT/OSC2/RA6_7") (pintype "bidirectional"))
    )
    (net (code "58") (name "QEIA2_1") (class "Default")
      (node (ref "MOTORA_2") (pin "5") (pinfunction "S_5") (pintype "passive"))
      (node (ref "U$4") (pin "19") (pinfunction "RB1/AN10/CPS1_19") (pintype "bidirectional"))
    )
    (net (code "59") (name "QEIA2_2") (class "Default")
      (node (ref "MOTORA_2") (pin "6") (pinfunction "S_6") (pintype "passive"))
      (node (ref "U$4") (pin "18") (pinfunction "RB0/AN12/CPS0/INT_18") (pintype "bidirectional"))
    )
    (net (code "60") (name "QEIB1_1") (class "Default")
      (node (ref "MOTORB_1") (pin "5") (pinfunction "S_5") (pintype "passive"))
      (node (ref "U$4") (pin "3") (pinfunction "T0CKI/CPS6/RA4_3") (pintype "bidirectional"))
    )
    (net (code "61") (name "QEIB1_2") (class "Default")
      (node (ref "MOTORB_1") (pin "6") (pinfunction "S_6") (pintype "passive"))
      (node (ref "U$4") (pin "4") (pinfunction "VCAP/~{SS/CPS7/AN4/RA5}_4") (pintype "bidirectional"))
    )
    (net (code "62") (name "QEIB2_1") (class "Default")
      (node (ref "MOTORB_2") (pin "5") (pinfunction "S_5") (pintype "passive"))
      (node (ref "U$4") (pin "21") (pinfunction "RB3/AN9/CPS3/CCP2_21") (pintype "bidirectional"))
    )
    (net (code "63") (name "QEIB2_2") (class "Default")
      (node (ref "MOTORB_2") (pin "6") (pinfunction "S_6") (pintype "passive"))
      (node (ref "U$4") (pin "20") (pinfunction "RB2/AN8/CPS2_20") (pintype "bidirectional"))
    )
    (net (code "64") (name "RX") (class "Default")
      (node (ref "FTDI") (pin "26") (pinfunction "TXD_26") (pintype "output"))
      (node (ref "U$4") (pin "22") (pinfunction "RB4/AN11/CPS4_22") (pintype "bidirectional"))
    )
    (net (code "65") (name "STATUS1") (class "Default")
      (node (ref "R1") (pin "2") (pinfunction "2_2") (pintype "passive"))
      (node (ref "U$4") (pin "27") (pinfunction "RA0/AN0/~{SS/VCAP}_27") (pintype "bidirectional"))
    )
    (net (code "66") (name "TX") (class "Default")
      (node (ref "FTDI") (pin "25") (pinfunction "RXD_25") (pintype "input"))
      (node (ref "U$4") (pin "23") (pinfunction "RB5/AN13/CPS5/T1G_23") (pintype "bidirectional"))
    )
    (net (code "67") (name "V3P3_1") (class "Default")
      (node (ref "C11") (pin "1") (pinfunction "1_1") (pintype "passive"))
      (node (ref "R10") (pin "2") (pinfunction "2_2") (pintype "passive"))
      (node (ref "R8") (pin "1") (pinfunction "1_1") (pintype "passive"))
      (node (ref "U$2") (pin "15") (pinfunction "V3P3_15") (pintype "bidirectional"))
    )
    (net (code "68") (name "V3P3_2") (class "Default")
      (node (ref "C17") (pin "1") (pinfunction "1_1") (pintype "passive"))
      (node (ref "R13") (pin "1") (pinfunction "1_1") (pintype "passive"))
      (node (ref "R15") (pin "2") (pinfunction "2_2") (pintype "passive"))
      (node (ref "U$3") (pin "15") (pinfunction "V3P3_15") (pintype "bidirectional"))
    )
    (net (code "69") (name "VBUS") (class "Default")
      (node (ref "BT_USB_MICROB1") (pin "VBUS") (pinfunction "VBUS_VBUS") (pintype "bidirectional"))
      (node (ref "FTDI") (pin "8") (pinfunction "VBUS_8") (pintype "input"))
      (node (ref "JP1") (pin "1") (pinfunction "1_1") (pintype "passive"))
      (node (ref "R47") (pin "2") (pinfunction "2_2") (pintype "passive"))
    )
    (net (code "70") (name "unconnected-(BT_USB_MICROB1-PadID)") (class "Default")
      (node (ref "BT_USB_MICROB1") (pin "ID") (pinfunction "ID_ID") (pintype "bidirectional"))
    )
    (net (code "71") (name "unconnected-(JP11-Pad6)") (class "Default")
      (node (ref "JP11") (pin "6") (pinfunction "6_6") (pintype "passive"))
    )
    (net (code "72") (name "unconnected-(RST_JMPR-Pad1)") (class "Default")
      (node (ref "RST_JMPR") (pin "1") (pinfunction "1_1") (pintype "passive"))
    )
    (net (code "73") (name "unconnected-(U$2-ADECAY-Pad20)") (class "Default")
      (node (ref "U$2") (pin "20") (pinfunction "ADECAY_20") (pintype "bidirectional"))
    )
    (net (code "74") (name "unconnected-(U$2-BDECAY-Pad19)") (class "Default")
      (node (ref "U$2") (pin "19") (pinfunction "BDECAY_19") (pintype "bidirectional"))
    )
    (net (code "75") (name "unconnected-(U$2-TOFF-Pad16)") (class "Default")
      (node (ref "U$2") (pin "16") (pinfunction "TOFF_16") (pintype "bidirectional"))
    )
    (net (code "76") (name "unconnected-(U$3-ADECAY-Pad20)") (class "Default")
      (node (ref "U$3") (pin "20") (pinfunction "ADECAY_20") (pintype "bidirectional"))
    )
    (net (code "77") (name "unconnected-(U$3-BDECAY-Pad19)") (class "Default")
      (node (ref "U$3") (pin "19") (pinfunction "BDECAY_19") (pintype "bidirectional"))
    )
    (net (code "78") (name "unconnected-(U$3-TOFF-Pad16)") (class "Default")
      (node (ref "U$3") (pin "16") (pinfunction "TOFF_16") (pintype "bidirectional"))
    )
    (net (code "79") (name "unconnected-(U$4-CK{slash}TX{slash}RC6-Pad14)") (class "Default")
      (node (ref "U$4") (pin "14") (pinfunction "CK/TX/RC6_14") (pintype "bidirectional"))
    )
  )
)
